# Microcontroller.net
KiCad netlist of a schematic drawn in Altium Designer
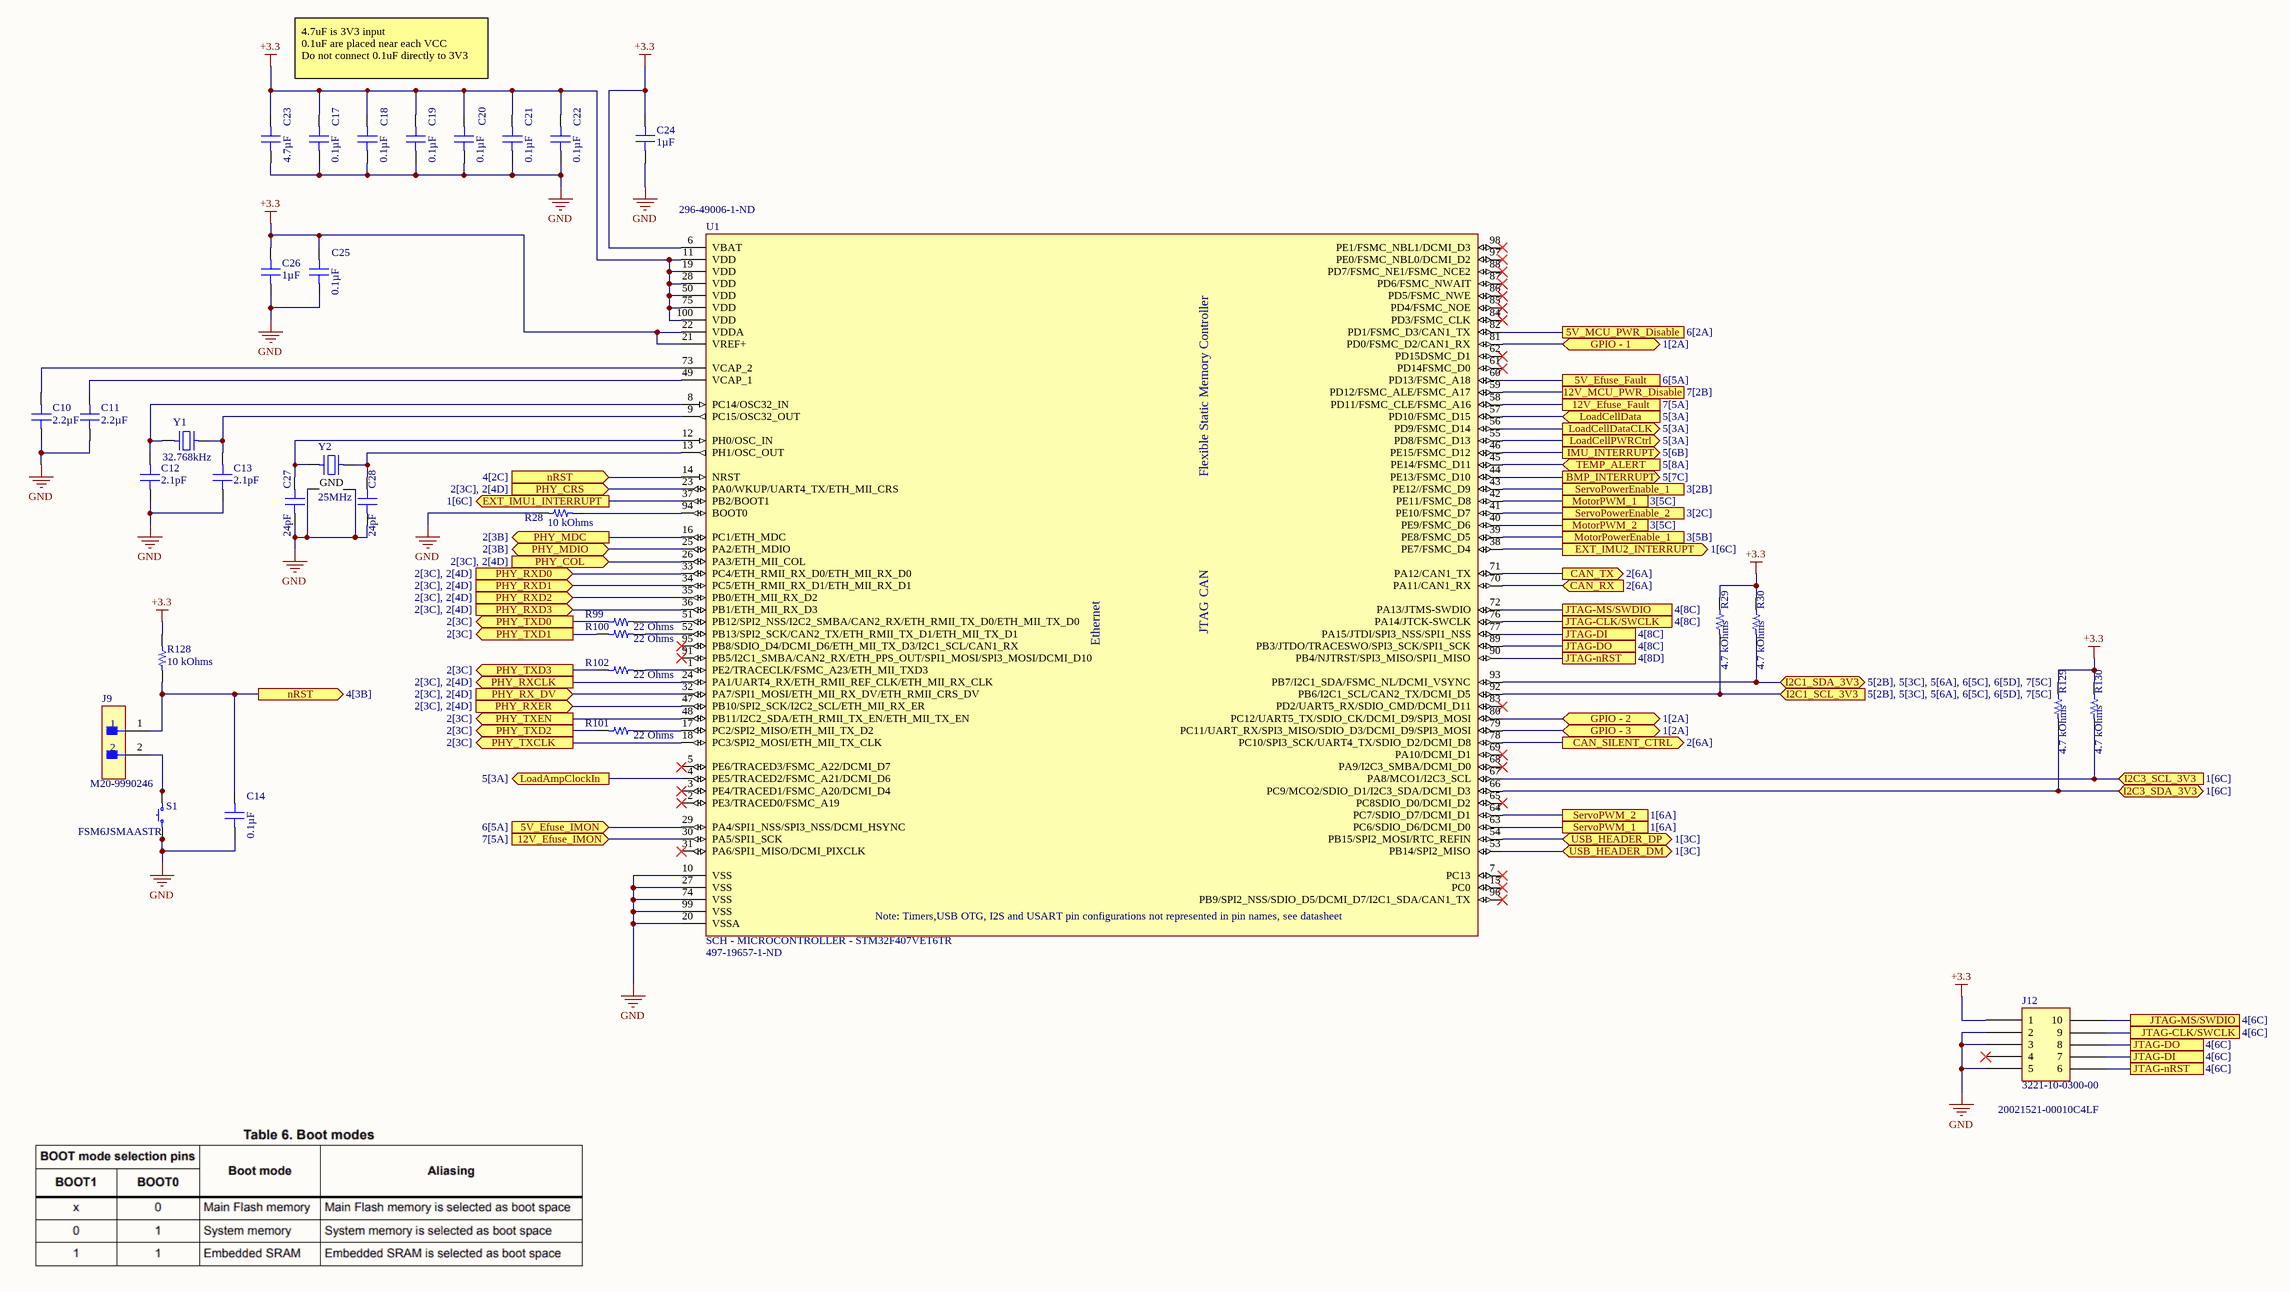
[diagram p0: Microcontroller.SchDoc]

(export (version "E")
  (design (tool "Eeschema 10.0.6"))
  (components
    (comp (ref "C10")
      (value "2.2µF")
      (footprint "CAP 0603_1608")
      (description "CAP CER 2.2UF 16V X5R 0603")
      (fields (field (name "PART NUMBER") "EMK107BJ225KA-T") (field (name "MANUFACTURER") "Taiyo Yuden"))
      (libsource (lib "Celestial Altium Library - altium_library") (part "Capacitor"))
    )
    (comp (ref "C11")
      (value "2.2µF")
      (footprint "CAP 0603_1608")
      (description "CAP CER 2.2UF 16V X5R 0603")
      (fields (field (name "PART NUMBER") "EMK107BJ225KA-T") (field (name "MANUFACTURER") "Taiyo Yuden"))
      (libsource (lib "Celestial Altium Library - altium_library") (part "Capacitor"))
    )
    (comp (ref "C12")
      (value "2.1pF")
      (footprint "CAP 0603_1608")
      (description "CAP CER RF 2.1PF 50V +/-0.1 PF C")
      (fields (field (name "PART NUMBER") "CBR06C219B5GAC") (field (name "MANUFACTURER") "KEMET"))
      (libsource (lib "Celestial Altium Library - altium_library") (part "Capacitor"))
    )
    (comp (ref "C13")
      (value "2.1pF")
      (footprint "CAP 0603_1608")
      (description "CAP CER RF 2.1PF 50V +/-0.1 PF C")
      (fields (field (name "PART NUMBER") "CBR06C219B5GAC") (field (name "MANUFACTURER") "KEMET"))
      (libsource (lib "Celestial Altium Library - altium_library") (part "Capacitor"))
    )
    (comp (ref "C14")
      (value "0.1µF")
      (footprint "CAP 0603_1608")
      (description "CAP CER 0.1UF 25V X7R 0603")
      (fields
        (field (name "PART NUMBER") "CL10B104KA8WPNC")
        (field (name "MANUFACTURER") "Samsung Electro-Mechanics")
      )
      (libsource (lib "Celestial Altium Library - altium_library") (part "Capacitor"))
    )
    (comp (ref "C17")
      (value "0.1µF")
      (footprint "CAP 0603_1608")
      (description "CAP CER 0.1UF 25V X7R 0603")
      (fields
        (field (name "PART NUMBER") "CL10B104KA8WPNC")
        (field (name "MANUFACTURER") "Samsung Electro-Mechanics")
      )
      (libsource (lib "Celestial Altium Library - altium_library") (part "Capacitor"))
    )
    (comp (ref "C18")
      (value "0.1µF")
      (footprint "CAP 0603_1608")
      (description "CAP CER 0.1UF 25V X7R 0603")
      (fields
        (field (name "PART NUMBER") "CL10B104KA8WPNC")
        (field (name "MANUFACTURER") "Samsung Electro-Mechanics")
      )
      (libsource (lib "Celestial Altium Library - altium_library") (part "Capacitor"))
    )
    (comp (ref "C19")
      (value "0.1µF")
      (footprint "CAP 0603_1608")
      (description "CAP CER 0.1UF 25V X7R 0603")
      (fields
        (field (name "PART NUMBER") "CL10B104KA8WPNC")
        (field (name "MANUFACTURER") "Samsung Electro-Mechanics")
      )
      (libsource (lib "Celestial Altium Library - altium_library") (part "Capacitor"))
    )
    (comp (ref "C20")
      (value "0.1µF")
      (footprint "CAP 0603_1608")
      (description "CAP CER 0.1UF 25V X7R 0603")
      (fields
        (field (name "PART NUMBER") "CL10B104KA8WPNC")
        (field (name "MANUFACTURER") "Samsung Electro-Mechanics")
      )
      (libsource (lib "Celestial Altium Library - altium_library") (part "Capacitor"))
    )
    (comp (ref "C21")
      (value "0.1µF")
      (footprint "CAP 0603_1608")
      (description "CAP CER 0.1UF 25V X7R 0603")
      (fields
        (field (name "PART NUMBER") "CL10B104KA8WPNC")
        (field (name "MANUFACTURER") "Samsung Electro-Mechanics")
      )
      (libsource (lib "Celestial Altium Library - altium_library") (part "Capacitor"))
    )
    (comp (ref "C22")
      (value "0.1µF")
      (footprint "CAP 0603_1608")
      (description "CAP CER 0.1UF 25V X7R 0603")
      (fields
        (field (name "PART NUMBER") "CL10B104KA8WPNC")
        (field (name "MANUFACTURER") "Samsung Electro-Mechanics")
      )
      (libsource (lib "Celestial Altium Library - altium_library") (part "Capacitor"))
    )
    (comp (ref "C23")
      (value "4.7µF")
      (footprint "CAP 0603_1608")
      (description "CAP CER 4.7UF 16V X5R 0603")
      (fields
        (field (name "PART NUMBER") "C1608X5R1C475K080AC")
        (field (name "MANUFACTURER") "TDK Corporation")
      )
      (libsource (lib "Celestial Altium Library - altium_library") (part "Capacitor"))
    )
    (comp (ref "C24")
      (value "1µF")
      (footprint "CAP 0603_1608")
      (description "CAP CER 1UF 16V X7R 0603")
      (fields
        (field (name "PART NUMBER") "GCM188R71C105KA64J")
        (field (name "MANUFACTURER") "Murata Electronics")
      )
      (libsource (lib "Celestial Altium Library - altium_library") (part "Capacitor"))
    )
    (comp (ref "C25")
      (value "0.1µF")
      (footprint "CAP 0603_1608")
      (description "CAP CER 0.1UF 25V X7R 0603")
      (fields
        (field (name "PART NUMBER") "CL10B104KA8WPNC")
        (field (name "MANUFACTURER") "Samsung Electro-Mechanics")
      )
      (libsource (lib "Celestial Altium Library - altium_library") (part "Capacitor"))
    )
    (comp (ref "C26")
      (value "1µF")
      (footprint "CAP 0603_1608")
      (description "CAP CER 1UF 16V X7R 0603")
      (fields
        (field (name "PART NUMBER") "GCM188R71C105KA64J")
        (field (name "MANUFACTURER") "Murata Electronics")
      )
      (libsource (lib "Celestial Altium Library - altium_library") (part "Capacitor"))
    )
    (comp (ref "C27")
      (value "24pF")
      (footprint "CAP 0603_1608")
      (description "CAP CER 24PF 50V C0G/NP0 0603")
      (fields
        (field (name "PART NUMBER") "CL10C240JB8NNNC")
        (field (name "MANUFACTURER") "Samsung Electro-Mechanics")
      )
      (libsource (lib "Celestial Altium Library - altium_library") (part "Capacitor"))
    )
    (comp (ref "C28")
      (value "24pF")
      (footprint "CAP 0603_1608")
      (description "CAP CER 24PF 50V C0G/NP0 0603")
      (fields
        (field (name "PART NUMBER") "CL10C240JB8NNNC")
        (field (name "MANUFACTURER") "Samsung Electro-Mechanics")
      )
      (libsource (lib "Celestial Altium Library - altium_library") (part "Capacitor"))
    )
    (comp (ref "J9")
      (value "M20-9990246")
      (footprint "FP-M20-9990246-MFG")
      (description "CONN HEADER VERT 2POS 2.54MM")
      (fields
        (field (name "OCTOPART") "https://octopart.com/m20-9990246-harwin-2590635")
        (field (name "MANUFACTURER") "Harwin")
      )
      (libsource (lib "Altium Content Vault") (part "3bc925449376181038e59eaffc5286c"))
    )
    (comp (ref "J12")
      (value "3221-10-0300-00")
      (footprint "CNC TECH 3221-10-0300-00")
      (description "CONN HEADER SMD 10POS 1.27MM")
      (fields (field (name "MANUFACTURER") "CNC Tech"))
      (libsource (lib "Celestial Altium Library - altium_library") (part "2x5 Pin"))
    )
    (comp (ref "R28")
      (value "10 kOhms")
      (footprint "RES 0603_1608")
      (description "RES 10K OHM 5% 1/10W 0603")
      (fields
        (field (name "PART NUMBER") "RMCF0603JT10K0")
        (field (name "MANUFACTURER") "Stackpole Electronics Inc")
      )
      (libsource (lib "Celestial Altium Library - altium_library") (part "Resistor"))
    )
    (comp (ref "R29")
      (value "4.7 kOhms")
      (footprint "RES 0603_1608")
      (description "RES 4.7K OHM 1% 1/10W 0603")
      (fields
        (field (name "PART NUMBER") "RMCF0603FT4K70")
        (field (name "MANUFACTURER") "Stackpole Electronics Inc")
      )
      (libsource (lib "Celestial Altium Library - altium_library") (part "Resistor"))
    )
    (comp (ref "R30")
      (value "4.7 kOhms")
      (footprint "RES 0603_1608")
      (description "RES 4.7K OHM 1% 1/10W 0603")
      (fields
        (field (name "PART NUMBER") "RMCF0603FT4K70")
        (field (name "MANUFACTURER") "Stackpole Electronics Inc")
      )
      (libsource (lib "Celestial Altium Library - altium_library") (part "Resistor"))
    )
    (comp (ref "R99")
      (value "22 Ohms")
      (footprint "RES 0603_1608")
      (description "RES 22 OHM 1% 1/10W 0603")
      (fields
        (field (name "PART NUMBER") "RMCF0603FT22R0")
        (field (name "MANUFACTURER") "Stackpole Electronics Inc")
      )
      (libsource (lib "Celestial Altium Library - altium_library") (part "Resistor"))
    )
    (comp (ref "R100")
      (value "22 Ohms")
      (footprint "RES 0603_1608")
      (description "RES 22 OHM 1% 1/10W 0603")
      (fields
        (field (name "PART NUMBER") "RMCF0603FT22R0")
        (field (name "MANUFACTURER") "Stackpole Electronics Inc")
      )
      (libsource (lib "Celestial Altium Library - altium_library") (part "Resistor"))
    )
    (comp (ref "R101")
      (value "22 Ohms")
      (footprint "RES 0603_1608")
      (description "RES 22 OHM 1% 1/10W 0603")
      (fields
        (field (name "PART NUMBER") "RMCF0603FT22R0")
        (field (name "MANUFACTURER") "Stackpole Electronics Inc")
      )
      (libsource (lib "Celestial Altium Library - altium_library") (part "Resistor"))
    )
    (comp (ref "R102")
      (value "22 Ohms")
      (footprint "RES 0603_1608")
      (description "RES 22 OHM 1% 1/10W 0603")
      (fields
        (field (name "PART NUMBER") "RMCF0603FT22R0")
        (field (name "MANUFACTURER") "Stackpole Electronics Inc")
      )
      (libsource (lib "Celestial Altium Library - altium_library") (part "Resistor"))
    )
    (comp (ref "R128")
      (value "10 kOhms")
      (footprint "RES 0603_1608")
      (description "RES 10K OHM 5% 1/10W 0603")
      (fields
        (field (name "PART NUMBER") "RMCF0603JT10K0")
        (field (name "MANUFACTURER") "Stackpole Electronics Inc")
      )
      (libsource (lib "Celestial Altium Library - altium_library") (part "Resistor"))
    )
    (comp (ref "R129")
      (value "4.7 kOhms")
      (footprint "RES 0603_1608")
      (description "RES 4.7K OHM 1% 1/10W 0603")
      (fields
        (field (name "PART NUMBER") "RMCF0603FT4K70")
        (field (name "MANUFACTURER") "Stackpole Electronics Inc")
      )
      (libsource (lib "Celestial Altium Library - altium_library") (part "Resistor"))
    )
    (comp (ref "R130")
      (value "4.7 kOhms")
      (footprint "RES 0603_1608")
      (description "RES 4.7K OHM 1% 1/10W 0603")
      (fields
        (field (name "PART NUMBER") "RMCF0603FT4K70")
        (field (name "MANUFACTURER") "Stackpole Electronics Inc")
      )
      (libsource (lib "Celestial Altium Library - altium_library") (part "Resistor"))
    )
    (comp (ref "S1")
      (value "FSM6JSMAASTR")
      (footprint "TE FSM6JSMA")
      (description "SWITCH TACTILE SPST-NO 0.05A 24V")
      (fields (field (name "MANUFACTURER") "TE Connectivity ALCOSWITCH Switches"))
      (libsource (lib "Celestial Altium Library - altium_library") (part "SPST-NO 4 PIN"))
    )
    (comp (ref "U1")
      (value "SCH - MICROCONTROLLER - STM32F407VET6TR")
      (footprint "PCB - LEADLESS - QFP - ST LQFP-100 14X14MM")
      (fields (field (name "SUPPLIER PART NUMBER 1") "497-19657-1-ND"))
      (libsource (lib "HAB_ICs") (part "SCH - MICROCONTROLLER - STM32F407VET6TR"))
    )
    (comp (ref "Y1")
      (value "32.768kHz")
      (footprint "ABRACON ABS07")
      (description "IOT 32.786KHZ XTAL")
      (fields
        (field (name "PART NUMBER") "ABS07-166-32.768KHZ-T")
        (field (name "MANUFACTURER") "Abracon LLC")
      )
      (libsource (lib "Celestial Altium Library - altium_library") (part "Abracon Crystal ABS07"))
    )
    (comp (ref "Y2")
      (value "25MHz")
      (footprint "EPSON TSX-3225")
      (description "CRYSTAL 25.0000MHZ 18PF SMD")
      (fields (field (name "PART NUMBER") "TSX-3225 25.0000MF20P-C0") (field (name "MANUFACTURER") "EPSON"))
      (libsource (lib "Celestial Altium Library - altium_library") (part "Epson Crystal TSX-3225"))
    )
  )
  (nets
    (net (code "1") (name "+3.3") (class "Default")
      (node (ref "C17") (pin "2") (pinfunction "2_2") (pintype "passive"))
      (node (ref "C18") (pin "2") (pinfunction "2_2") (pintype "passive"))
      (node (ref "C19") (pin "2") (pinfunction "2_2") (pintype "passive"))
      (node (ref "C20") (pin "2") (pinfunction "2_2") (pintype "passive"))
      (node (ref "C21") (pin "2") (pinfunction "2_2") (pintype "passive"))
      (node (ref "C22") (pin "2") (pinfunction "2_2") (pintype "passive"))
      (node (ref "C23") (pin "2") (pinfunction "2_2") (pintype "passive"))
      (node (ref "C24") (pin "2") (pinfunction "2_2") (pintype "passive"))
      (node (ref "C25") (pin "2") (pinfunction "2_2") (pintype "passive"))
      (node (ref "C26") (pin "2") (pinfunction "2_2") (pintype "passive"))
      (node (ref "J12") (pin "1") (pinfunction "1_1") (pintype "passive"))
      (node (ref "R128") (pin "1") (pinfunction "1_1") (pintype "passive"))
      (node (ref "R129") (pin "2") (pinfunction "2_2") (pintype "passive"))
      (node (ref "R130") (pin "2") (pinfunction "2_2") (pintype "passive"))
      (node (ref "R29") (pin "2") (pinfunction "2_2") (pintype "passive"))
      (node (ref "R30") (pin "2") (pinfunction "2_2") (pintype "passive"))
      (node (ref "U1") (pin "100") (pinfunction "VDD_100") (pintype "power_in"))
      (node (ref "U1") (pin "11") (pinfunction "VDD_11") (pintype "power_in"))
      (node (ref "U1") (pin "19") (pinfunction "VDD_19") (pintype "power_in"))
      (node (ref "U1") (pin "21") (pinfunction "VREF+_21") (pintype "power_in"))
      (node (ref "U1") (pin "22") (pinfunction "VDDA_22") (pintype "power_in"))
      (node (ref "U1") (pin "28") (pinfunction "VDD_28") (pintype "power_in"))
      (node (ref "U1") (pin "50") (pinfunction "VDD_50") (pintype "power_in"))
      (node (ref "U1") (pin "6") (pinfunction "VBAT_6") (pintype "power_in"))
      (node (ref "U1") (pin "75") (pinfunction "VDD_75") (pintype "power_in"))
    )
    (net (code "2") (name "/5V_Efuse_Fault") (class "Default")
      (node (ref "U1") (pin "60") (pinfunction "PD13/FSMC_A18_60") (pintype "bidirectional"))
    )
    (net (code "3") (name "/5V_Efuse_IMON") (class "Default")
      (node (ref "U1") (pin "29") (pinfunction "PA4/SPI1_NSS/SPI3_NSS/DCMI_HSYNC_29") (pintype "bidirectional"))
    )
    (net (code "4") (name "/5V_MCU_PWR_Disable") (class "Default")
      (node (ref "U1") (pin "82") (pinfunction "PD1/FSMC_D3/CAN1_TX_82") (pintype "bidirectional"))
    )
    (net (code "5") (name "/12V_Efuse_Fault") (class "Default")
      (node (ref "U1") (pin "58") (pinfunction "PD11/FSMC_CLE/FSMC_A16_58") (pintype "bidirectional"))
    )
    (net (code "6") (name "/12V_Efuse_IMON") (class "Default")
      (node (ref "U1") (pin "30") (pinfunction "PA5/SPI1_SCK_30") (pintype "bidirectional"))
    )
    (net (code "7") (name "/12V_MCU_PWR_Disable") (class "Default")
      (node (ref "U1") (pin "59") (pinfunction "PD12/FSMC_ALE/FSMC_A17_59") (pintype "bidirectional"))
    )
    (net (code "8") (name "/BMP_INTERRUPT") (class "Default")
      (node (ref "U1") (pin "44") (pinfunction "PE13/FSMC_D10_44") (pintype "bidirectional"))
    )
    (net (code "9") (name "/CAN_RX") (class "Default")
      (node (ref "U1") (pin "70") (pinfunction "PA11/CAN1_RX_70") (pintype "bidirectional"))
    )
    (net (code "10") (name "/CAN_SILENT_CTRL") (class "Default")
      (node (ref "U1") (pin "78") (pinfunction "PC10/SPI3_SCK/UART4_TX/SDIO_D2/DCMI_D8_78") (pintype "bidirectional"))
    )
    (net (code "11") (name "/CAN_TX") (class "Default")
      (node (ref "U1") (pin "71") (pinfunction "PA12/CAN1_TX_71") (pintype "bidirectional"))
    )
    (net (code "12") (name "/EXT_IMU1_INTERRUPT") (class "Default")
      (node (ref "U1") (pin "37") (pinfunction "PB2/BOOT1_37") (pintype "bidirectional"))
    )
    (net (code "13") (name "/EXT_IMU2_INTERRUPT") (class "Default")
      (node (ref "U1") (pin "38") (pinfunction "PE7/FSMC_D4_38") (pintype "bidirectional"))
    )
    (net (code "14") (name "/GPIO - 1") (class "Default")
      (node (ref "U1") (pin "81") (pinfunction "PD0/FSMC_D2/CAN1_RX_81") (pintype "bidirectional"))
    )
    (net (code "15") (name "/GPIO - 2") (class "Default")
      (node (ref "U1") (pin "80") (pinfunction "PC12/UART5_TX/SDIO_CK/DCMI_D9/SPI3_MOSI_80") (pintype "bidirectional"))
    )
    (net (code "16") (name "/GPIO - 3") (class "Default")
      (node (ref "U1") (pin "79") (pinfunction "PC11/UART_RX/SPI3_MISO/SDIO_D3/DCMI_D9/SPI3_MOSI_79") (pintype "bidirectional"))
    )
    (net (code "17") (name "/I2C1_SCL_3V3") (class "Default")
      (node (ref "R29") (pin "1") (pinfunction "1_1") (pintype "passive"))
      (node (ref "U1") (pin "92") (pinfunction "PB6/I2C1_SCL/CAN2_TX/DCMI_D5_92") (pintype "bidirectional"))
    )
    (net (code "18") (name "/I2C1_SDA_3V3") (class "Default")
      (node (ref "R30") (pin "1") (pinfunction "1_1") (pintype "passive"))
      (node (ref "U1") (pin "93") (pinfunction "PB7/I2C1_SDA/FSMC_NL/DCMI_VSYNC_93") (pintype "bidirectional"))
    )
    (net (code "19") (name "/I2C3_SCL_3V3") (class "Default")
      (node (ref "R130") (pin "1") (pinfunction "1_1") (pintype "passive"))
      (node (ref "U1") (pin "67") (pinfunction "PA8/MCO1/I2C3_SCL_67") (pintype "bidirectional"))
    )
    (net (code "20") (name "/I2C3_SDA_3V3") (class "Default")
      (node (ref "R129") (pin "1") (pinfunction "1_1") (pintype "passive"))
      (node (ref "U1") (pin "66") (pinfunction "PC9/MCO2/SDIO_D1/I2C3_SDA/DCMI_D3_66") (pintype "bidirectional"))
    )
    (net (code "21") (name "/IMU_INTERRUPT") (class "Default")
      (node (ref "U1") (pin "46") (pinfunction "PE15/FSMC_D12_46") (pintype "bidirectional"))
    )
    (net (code "22") (name "/JTAG-CLK{slash}SWCLK") (class "Default")
      (node (ref "J12") (pin "9") (pinfunction "9_9") (pintype "passive"))
      (node (ref "U1") (pin "76") (pinfunction "PA14/JTCK-SWCLK_76") (pintype "bidirectional"))
    )
    (net (code "23") (name "/JTAG-DI") (class "Default")
      (node (ref "J12") (pin "7") (pinfunction "7_7") (pintype "passive"))
      (node (ref "U1") (pin "77") (pinfunction "PA15/JTDI/SPI3_NSS/SPI1_NSS_77") (pintype "bidirectional"))
    )
    (net (code "24") (name "/JTAG-DO") (class "Default")
      (node (ref "J12") (pin "8") (pinfunction "8_8") (pintype "passive"))
      (node (ref "U1") (pin "89") (pinfunction "PB3/JTDO/TRACESWO/SPI3_SCK/SPI1_SCK_89") (pintype "bidirectional"))
    )
    (net (code "25") (name "/JTAG-MS{slash}SWDIO") (class "Default")
      (node (ref "J12") (pin "10") (pinfunction "10_10") (pintype "passive"))
      (node (ref "U1") (pin "72") (pinfunction "PA13/JTMS-SWDIO_72") (pintype "bidirectional"))
    )
    (net (code "26") (name "/JTAG-nRST") (class "Default")
      (node (ref "J12") (pin "6") (pinfunction "6_6") (pintype "passive"))
      (node (ref "U1") (pin "90") (pinfunction "PB4/NJTRST/SPI3_MISO/SPI1_MISO_90") (pintype "bidirectional"))
    )
    (net (code "27") (name "/LoadAmpClockIn") (class "Default")
      (node (ref "U1") (pin "4") (pinfunction "PE5/TRACED2/FSMC_A21/DCMI_D6_4") (pintype "bidirectional"))
    )
    (net (code "28") (name "/LoadCellData") (class "Default")
      (node (ref "U1") (pin "57") (pinfunction "PD10/FSMC_D15_57") (pintype "bidirectional"))
    )
    (net (code "29") (name "/LoadCellDataCLK") (class "Default")
      (node (ref "U1") (pin "56") (pinfunction "PD9/FSMC_D14_56") (pintype "bidirectional"))
    )
    (net (code "30") (name "/LoadCellPWRCtrl") (class "Default")
      (node (ref "U1") (pin "55") (pinfunction "PD8/FSMC_D13_55") (pintype "bidirectional"))
    )
    (net (code "31") (name "/MotorPWM_1") (class "Default")
      (node (ref "U1") (pin "42") (pinfunction "PE11/FSMC_D8_42") (pintype "bidirectional"))
    )
    (net (code "32") (name "/MotorPWM_2") (class "Default")
      (node (ref "U1") (pin "40") (pinfunction "PE9/FSMC_D6_40") (pintype "bidirectional"))
    )
    (net (code "33") (name "/MotorPowerEnable_1") (class "Default")
      (node (ref "U1") (pin "39") (pinfunction "PE8/FSMC_D5_39") (pintype "bidirectional"))
    )
    (net (code "34") (name "/PHY_COL") (class "Default")
      (node (ref "U1") (pin "26") (pinfunction "PA3/ETH_MII_COL_26") (pintype "bidirectional"))
    )
    (net (code "35") (name "/PHY_CRS") (class "Default")
      (node (ref "U1") (pin "23") (pinfunction "PA0/WKUP/UART4_TX/ETH_MII_CRS_23") (pintype "bidirectional"))
    )
    (net (code "36") (name "/PHY_MDC") (class "Default")
      (node (ref "U1") (pin "16") (pinfunction "PC1/ETH_MDC_16") (pintype "bidirectional"))
    )
    (net (code "37") (name "/PHY_MDIO") (class "Default")
      (node (ref "U1") (pin "25") (pinfunction "PA2/ETH_MDIO_25") (pintype "bidirectional"))
    )
    (net (code "38") (name "/PHY_RXCLK") (class "Default")
      (node (ref "U1") (pin "24") (pinfunction "PA1/UART4_RX/ETH_RMII_REF_CLK/ETH_MII_RX_CLK_24") (pintype "bidirectional"))
    )
    (net (code "39") (name "/PHY_RXD0") (class "Default")
      (node (ref "U1") (pin "33") (pinfunction "PC4/ETH_RMII_RX_D0/ETH_MII_RX_D0_33") (pintype "bidirectional"))
    )
    (net (code "40") (name "/PHY_RXD1") (class "Default")
      (node (ref "U1") (pin "34") (pinfunction "PC5/ETH_RMII_RX_D1/ETH_MII_RX_D1_34") (pintype "bidirectional"))
    )
    (net (code "41") (name "/PHY_RXD2") (class "Default")
      (node (ref "U1") (pin "35") (pinfunction "PB0/ETH_MII_RX_D2_35") (pintype "bidirectional"))
    )
    (net (code "42") (name "/PHY_RXD3") (class "Default")
      (node (ref "U1") (pin "36") (pinfunction "PB1/ETH_MII_RX_D3_36") (pintype "bidirectional"))
    )
    (net (code "43") (name "/PHY_RXER") (class "Default")
      (node (ref "U1") (pin "47") (pinfunction "PB10/SPI2_SCK/I2C2_SCL/ETH_MII_RX_ER_47") (pintype "bidirectional"))
    )
    (net (code "44") (name "/PHY_RX_DV") (class "Default")
      (node (ref "U1") (pin "32") (pinfunction "PA7/SPI1_MOSI/ETH_MII_RX_DV/ETH_RMII_CRS_DV_32") (pintype "bidirectional"))
    )
    (net (code "45") (name "/PHY_TXCLK") (class "Default")
      (node (ref "U1") (pin "18") (pinfunction "PC3/SPI2_MOSI/ETH_MII_TX_CLK_18") (pintype "bidirectional"))
    )
    (net (code "46") (name "/PHY_TXD0") (class "Default")
      (node (ref "R99") (pin "1") (pinfunction "1_1") (pintype "passive"))
    )
    (net (code "47") (name "/PHY_TXD1") (class "Default")
      (node (ref "R100") (pin "1") (pinfunction "1_1") (pintype "passive"))
    )
    (net (code "48") (name "/PHY_TXD2") (class "Default")
      (node (ref "R101") (pin "1") (pinfunction "1_1") (pintype "passive"))
    )
    (net (code "49") (name "/PHY_TXD3") (class "Default")
      (node (ref "R102") (pin "1") (pinfunction "1_1") (pintype "passive"))
    )
    (net (code "50") (name "/PHY_TXEN") (class "Default")
      (node (ref "U1") (pin "48") (pinfunction "PB11/I2C2_SDA/ETH_RMII_TX_EN/ETH_MII_TX_EN_48") (pintype "bidirectional"))
    )
    (net (code "51") (name "/ServoPWM_1") (class "Default")
      (node (ref "U1") (pin "63") (pinfunction "PC6/SDIO_D6/DCMI_D0_63") (pintype "bidirectional"))
    )
    (net (code "52") (name "/ServoPWM_2") (class "Default")
      (node (ref "U1") (pin "64") (pinfunction "PC7/SDIO_D7/DCMI_D1_64") (pintype "bidirectional"))
    )
    (net (code "53") (name "/ServoPowerEnable_1") (class "Default")
      (node (ref "U1") (pin "43") (pinfunction "PE12//FSMC_D9_43") (pintype "bidirectional"))
    )
    (net (code "54") (name "/ServoPowerEnable_2") (class "Default")
      (node (ref "U1") (pin "41") (pinfunction "PE10/FSMC_D7_41") (pintype "bidirectional"))
    )
    (net (code "55") (name "/TEMP_ALERT") (class "Default")
      (node (ref "U1") (pin "45") (pinfunction "PE14/FSMC_D11_45") (pintype "bidirectional"))
    )
    (net (code "56") (name "/USB_HEADER_DM") (class "Default")
      (node (ref "U1") (pin "53") (pinfunction "PB14/SPI2_MISO_53") (pintype "bidirectional"))
    )
    (net (code "57") (name "/USB_HEADER_DP") (class "Default")
      (node (ref "U1") (pin "54") (pinfunction "PB15/SPI2_MOSI/RTC_REFIN_54") (pintype "bidirectional"))
    )
    (net (code "58") (name "/nRST") (class "Default")
      (node (ref "C14") (pin "2") (pinfunction "2_2") (pintype "passive"))
      (node (ref "J9") (pin "1") (pinfunction "1_1") (pintype "passive"))
      (node (ref "R128") (pin "2") (pinfunction "2_2") (pintype "passive"))
      (node (ref "U1") (pin "14") (pinfunction "NRST_14") (pintype "input"))
    )
    (net (code "59") (name "GND") (class "Default")
      (node (ref "C10") (pin "1") (pinfunction "1_1") (pintype "passive"))
      (node (ref "C11") (pin "1") (pinfunction "1_1") (pintype "passive"))
      (node (ref "C12") (pin "1") (pinfunction "1_1") (pintype "passive"))
      (node (ref "C13") (pin "1") (pinfunction "1_1") (pintype "passive"))
      (node (ref "C14") (pin "1") (pinfunction "1_1") (pintype "passive"))
      (node (ref "C17") (pin "1") (pinfunction "1_1") (pintype "passive"))
      (node (ref "C18") (pin "1") (pinfunction "1_1") (pintype "passive"))
      (node (ref "C19") (pin "1") (pinfunction "1_1") (pintype "passive"))
      (node (ref "C20") (pin "1") (pinfunction "1_1") (pintype "passive"))
      (node (ref "C21") (pin "1") (pinfunction "1_1") (pintype "passive"))
      (node (ref "C22") (pin "1") (pinfunction "1_1") (pintype "passive"))
      (node (ref "C23") (pin "1") (pinfunction "1_1") (pintype "passive"))
      (node (ref "C24") (pin "1") (pinfunction "1_1") (pintype "passive"))
      (node (ref "C25") (pin "1") (pinfunction "1_1") (pintype "passive"))
      (node (ref "C26") (pin "1") (pinfunction "1_1") (pintype "passive"))
      (node (ref "C27") (pin "1") (pinfunction "1_1") (pintype "passive"))
      (node (ref "C28") (pin "1") (pinfunction "1_1") (pintype "passive"))
      (node (ref "J12") (pin "2") (pinfunction "2_2") (pintype "passive"))
      (node (ref "J12") (pin "3") (pinfunction "3_3") (pintype "passive"))
      (node (ref "J12") (pin "5") (pinfunction "5_5") (pintype "passive"))
      (node (ref "R28") (pin "2") (pinfunction "2_2") (pintype "passive"))
      (node (ref "S1") (pin "1") (pinfunction "1_1") (pintype "passive"))
      (node (ref "S1") (pin "2") (pinfunction "2_2") (pintype "passive"))
      (node (ref "U1") (pin "10") (pinfunction "VSS_10") (pintype "power_in"))
      (node (ref "U1") (pin "20") (pinfunction "VSSA_20") (pintype "power_in"))
      (node (ref "U1") (pin "27") (pinfunction "VSS_27") (pintype "power_in"))
      (node (ref "U1") (pin "74") (pinfunction "VSS_74") (pintype "power_in"))
      (node (ref "U1") (pin "99") (pinfunction "VSS_99") (pintype "power_in"))
      (node (ref "Y2") (pin "2") (pinfunction "GND_2") (pintype "passive"))
      (node (ref "Y2") (pin "4") (pinfunction "GND_4") (pintype "passive"))
    )
    (net (code "60") (name "Net-(J9-Pad2)") (class "Default")
      (node (ref "J9") (pin "2") (pinfunction "2_2") (pintype "passive"))
      (node (ref "S1") (pin "3") (pinfunction "3_3") (pintype "passive"))
      (node (ref "S1") (pin "4") (pinfunction "4_4") (pintype "passive"))
    )
    (net (code "61") (name "Net-(U1-BOOT0)") (class "Default")
      (node (ref "R28") (pin "1") (pinfunction "1_1") (pintype "passive"))
      (node (ref "U1") (pin "94") (pinfunction "BOOT0_94") (pintype "bidirectional"))
    )
    (net (code "62") (name "Net-(U1-PB12{slash}SPI2_NSS{slash}I2C2_SMBA{slash}CAN2_RX{slash}ETH_RMII_TX_D0{slash}ETH_MII_TX_D0)") (class "Default")
      (node (ref "R99") (pin "2") (pinfunction "2_2") (pintype "passive"))
      (node (ref "U1") (pin "51") (pinfunction "PB12/SPI2_NSS/I2C2_SMBA/CAN2_RX/ETH_RMII_TX_D0/ETH_MII_TX_D0_51") (pintype "bidirectional"))
    )
    (net (code "63") (name "Net-(U1-PB13{slash}SPI2_SCK{slash}CAN2_TX{slash}ETH_RMII_TX_D1{slash}ETH_MII_TX_D1)") (class "Default")
      (node (ref "R100") (pin "2") (pinfunction "2_2") (pintype "passive"))
      (node (ref "U1") (pin "52") (pinfunction "PB13/SPI2_SCK/CAN2_TX/ETH_RMII_TX_D1/ETH_MII_TX_D1_52") (pintype "bidirectional"))
    )
    (net (code "64") (name "Net-(U1-PC2{slash}SPI2_MISO{slash}ETH_MII_TX_D2)") (class "Default")
      (node (ref "R101") (pin "2") (pinfunction "2_2") (pintype "passive"))
      (node (ref "U1") (pin "17") (pinfunction "PC2/SPI2_MISO/ETH_MII_TX_D2_17") (pintype "bidirectional"))
    )
    (net (code "65") (name "Net-(U1-PC14{slash}OSC32_IN)") (class "Default")
      (node (ref "C12") (pin "2") (pinfunction "2_2") (pintype "passive"))
      (node (ref "U1") (pin "8") (pinfunction "PC14/OSC32_IN_8") (pintype "input"))
      (node (ref "Y1") (pin "1") (pinfunction "1_1") (pintype "passive"))
    )
    (net (code "66") (name "Net-(U1-PC15{slash}OSC32_OUT)") (class "Default")
      (node (ref "C13") (pin "2") (pinfunction "2_2") (pintype "passive"))
      (node (ref "U1") (pin "9") (pinfunction "PC15/OSC32_OUT_9") (pintype "output"))
      (node (ref "Y1") (pin "2") (pinfunction "2_2") (pintype "passive"))
    )
    (net (code "67") (name "Net-(U1-PE2{slash}TRACECLK{slash}FSMC_A23{slash}ETH_MII_TXD3)") (class "Default")
      (node (ref "R102") (pin "2") (pinfunction "2_2") (pintype "passive"))
      (node (ref "U1") (pin "1") (pinfunction "PE2/TRACECLK/FSMC_A23/ETH_MII_TXD3_1") (pintype "bidirectional"))
    )
    (net (code "68") (name "Net-(U1-PH0{slash}OSC_IN)") (class "Default")
      (node (ref "C27") (pin "2") (pinfunction "2_2") (pintype "passive"))
      (node (ref "U1") (pin "12") (pinfunction "PH0/OSC_IN_12") (pintype "input"))
      (node (ref "Y2") (pin "1") (pinfunction "1_1") (pintype "passive"))
    )
    (net (code "69") (name "Net-(U1-PH1{slash}OSC_OUT)") (class "Default")
      (node (ref "C28") (pin "2") (pinfunction "2_2") (pintype "passive"))
      (node (ref "U1") (pin "13") (pinfunction "PH1/OSC_OUT_13") (pintype "output"))
      (node (ref "Y2") (pin "3") (pinfunction "3_3") (pintype "passive"))
    )
    (net (code "70") (name "Net-(U1-VCAP_1)") (class "Default")
      (node (ref "C11") (pin "2") (pinfunction "2_2") (pintype "passive"))
      (node (ref "U1") (pin "49") (pinfunction "VCAP_1_49") (pintype "power_in"))
    )
    (net (code "71") (name "Net-(U1-VCAP_2)") (class "Default")
      (node (ref "C10") (pin "2") (pinfunction "2_2") (pintype "passive"))
      (node (ref "U1") (pin "73") (pinfunction "VCAP_2_73") (pintype "power_in"))
    )
    (net (code "72") (name "unconnected-(J12-Pad4)") (class "Default")
      (node (ref "J12") (pin "4") (pinfunction "4_4") (pintype "passive+no_connect"))
    )
    (net (code "73") (name "unconnected-(U1-PA6{slash}SPI1_MISO{slash}DCMI_PIXCLK-Pad31)") (class "Default")
      (node (ref "U1") (pin "31") (pinfunction "PA6/SPI1_MISO/DCMI_PIXCLK_31") (pintype "bidirectional+no_connect"))
    )
    (net (code "74") (name "unconnected-(U1-PA9{slash}I2C3_SMBA{slash}DCMI_D0-Pad68)") (class "Default")
      (node (ref "U1") (pin "68") (pinfunction "PA9/I2C3_SMBA/DCMI_D0_68") (pintype "bidirectional+no_connect"))
    )
    (net (code "75") (name "unconnected-(U1-PA10{slash}DCMI_D1-Pad69)") (class "Default")
      (node (ref "U1") (pin "69") (pinfunction "PA10/DCMI_D1_69") (pintype "bidirectional+no_connect"))
    )
    (net (code "76") (name "unconnected-(U1-PB5{slash}I2C1_SMBA{slash}CAN2_RX{slash}ETH_PPS_OUT{slash}SPI1_MOSI{slash}SPI3_MOSI{slash}DCMI_D10-Pad91)") (class "Default")
      (node (ref "U1") (pin "91") (pinfunction "PB5/I2C1_SMBA/CAN2_RX/ETH_PPS_OUT/SPI1_MOSI/SPI3_MOSI/DCMI_D10_91") (pintype "bidirectional+no_connect"))
    )
    (net (code "77") (name "unconnected-(U1-PB8{slash}SDIO_D4{slash}DCMI_D6{slash}ETH_MII_TX_D3{slash}I2C1_SCL{slash}CAN1_RX-Pad95)") (class "Default")
      (node (ref "U1") (pin "95") (pinfunction "PB8/SDIO_D4/DCMI_D6/ETH_MII_TX_D3/I2C1_SCL/CAN1_RX_95") (pintype "bidirectional+no_connect"))
    )
    (net (code "78") (name "unconnected-(U1-PB9{slash}SPI2_NSS{slash}SDIO_D5{slash}DCMI_D7{slash}I2C1_SDA{slash}CAN1_TX-Pad96)") (class "Default")
      (node (ref "U1") (pin "96") (pinfunction "PB9/SPI2_NSS/SDIO_D5/DCMI_D7/I2C1_SDA/CAN1_TX_96") (pintype "bidirectional+no_connect"))
    )
    (net (code "79") (name "unconnected-(U1-PC0-Pad15)") (class "Default")
      (node (ref "U1") (pin "15") (pinfunction "PC0_15") (pintype "bidirectional+no_connect"))
    )
    (net (code "80") (name "unconnected-(U1-PC8SDIO_D0{slash}DCMI_D2-Pad65)") (class "Default")
      (node (ref "U1") (pin "65") (pinfunction "PC8SDIO_D0/DCMI_D2_65") (pintype "bidirectional+no_connect"))
    )
    (net (code "81") (name "unconnected-(U1-PC13-Pad7)") (class "Default")
      (node (ref "U1") (pin "7") (pinfunction "PC13_7") (pintype "bidirectional+no_connect"))
    )
    (net (code "82") (name "unconnected-(U1-PD2{slash}UART5_RX{slash}SDIO_CMD{slash}DCMI_D11-Pad83)") (class "Default")
      (node (ref "U1") (pin "83") (pinfunction "PD2/UART5_RX/SDIO_CMD/DCMI_D11_83") (pintype "bidirectional+no_connect"))
    )
    (net (code "83") (name "unconnected-(U1-PD3{slash}FSMC_CLK-Pad84)") (class "Default")
      (node (ref "U1") (pin "84") (pinfunction "PD3/FSMC_CLK_84") (pintype "bidirectional+no_connect"))
    )
    (net (code "84") (name "unconnected-(U1-PD4{slash}FSMC_NOE-Pad85)") (class "Default")
      (node (ref "U1") (pin "85") (pinfunction "PD4/FSMC_NOE_85") (pintype "bidirectional+no_connect"))
    )
    (net (code "85") (name "unconnected-(U1-PD5{slash}FSMC_NWE-Pad86)") (class "Default")
      (node (ref "U1") (pin "86") (pinfunction "PD5/FSMC_NWE_86") (pintype "bidirectional+no_connect"))
    )
    (net (code "86") (name "unconnected-(U1-PD6{slash}FSMC_NWAIT-Pad87)") (class "Default")
      (node (ref "U1") (pin "87") (pinfunction "PD6/FSMC_NWAIT_87") (pintype "bidirectional+no_connect"))
    )
    (net (code "87") (name "unconnected-(U1-PD7{slash}FSMC_NE1{slash}FSMC_NCE2-Pad88)") (class "Default")
      (node (ref "U1") (pin "88") (pinfunction "PD7/FSMC_NE1/FSMC_NCE2_88") (pintype "bidirectional+no_connect"))
    )
    (net (code "88") (name "unconnected-(U1-PD14FSMC_D0-Pad61)") (class "Default")
      (node (ref "U1") (pin "61") (pinfunction "PD14FSMC_D0_61") (pintype "bidirectional+no_connect"))
    )
    (net (code "89") (name "unconnected-(U1-PD15DSMC_D1-Pad62)") (class "Default")
      (node (ref "U1") (pin "62") (pinfunction "PD15DSMC_D1_62") (pintype "bidirectional+no_connect"))
    )
    (net (code "90") (name "unconnected-(U1-PE0{slash}FSMC_NBL0{slash}DCMI_D2-Pad97)") (class "Default")
      (node (ref "U1") (pin "97") (pinfunction "PE0/FSMC_NBL0/DCMI_D2_97") (pintype "bidirectional+no_connect"))
    )
    (net (code "91") (name "unconnected-(U1-PE1{slash}FSMC_NBL1{slash}DCMI_D3-Pad98)") (class "Default")
      (node (ref "U1") (pin "98") (pinfunction "PE1/FSMC_NBL1/DCMI_D3_98") (pintype "bidirectional+no_connect"))
    )
    (net (code "92") (name "unconnected-(U1-PE3{slash}TRACED0{slash}FSMC_A19-Pad2)") (class "Default")
      (node (ref "U1") (pin "2") (pinfunction "PE3/TRACED0/FSMC_A19_2") (pintype "bidirectional+no_connect"))
    )
    (net (code "93") (name "unconnected-(U1-PE4{slash}TRACED1{slash}FSMC_A20{slash}DCMI_D4-Pad3)") (class "Default")
      (node (ref "U1") (pin "3") (pinfunction "PE4/TRACED1/FSMC_A20/DCMI_D4_3") (pintype "bidirectional+no_connect"))
    )
    (net (code "94") (name "unconnected-(U1-PE6{slash}TRACED3{slash}FSMC_A22{slash}DCMI_D7-Pad5)") (class "Default")
      (node (ref "U1") (pin "5") (pinfunction "PE6/TRACED3/FSMC_A22/DCMI_D7_5") (pintype "bidirectional+no_connect"))
    )
  )
)
